# SCH_BlackRacer_team.net
KiCad netlist of a schematic drawn in EasyEDA
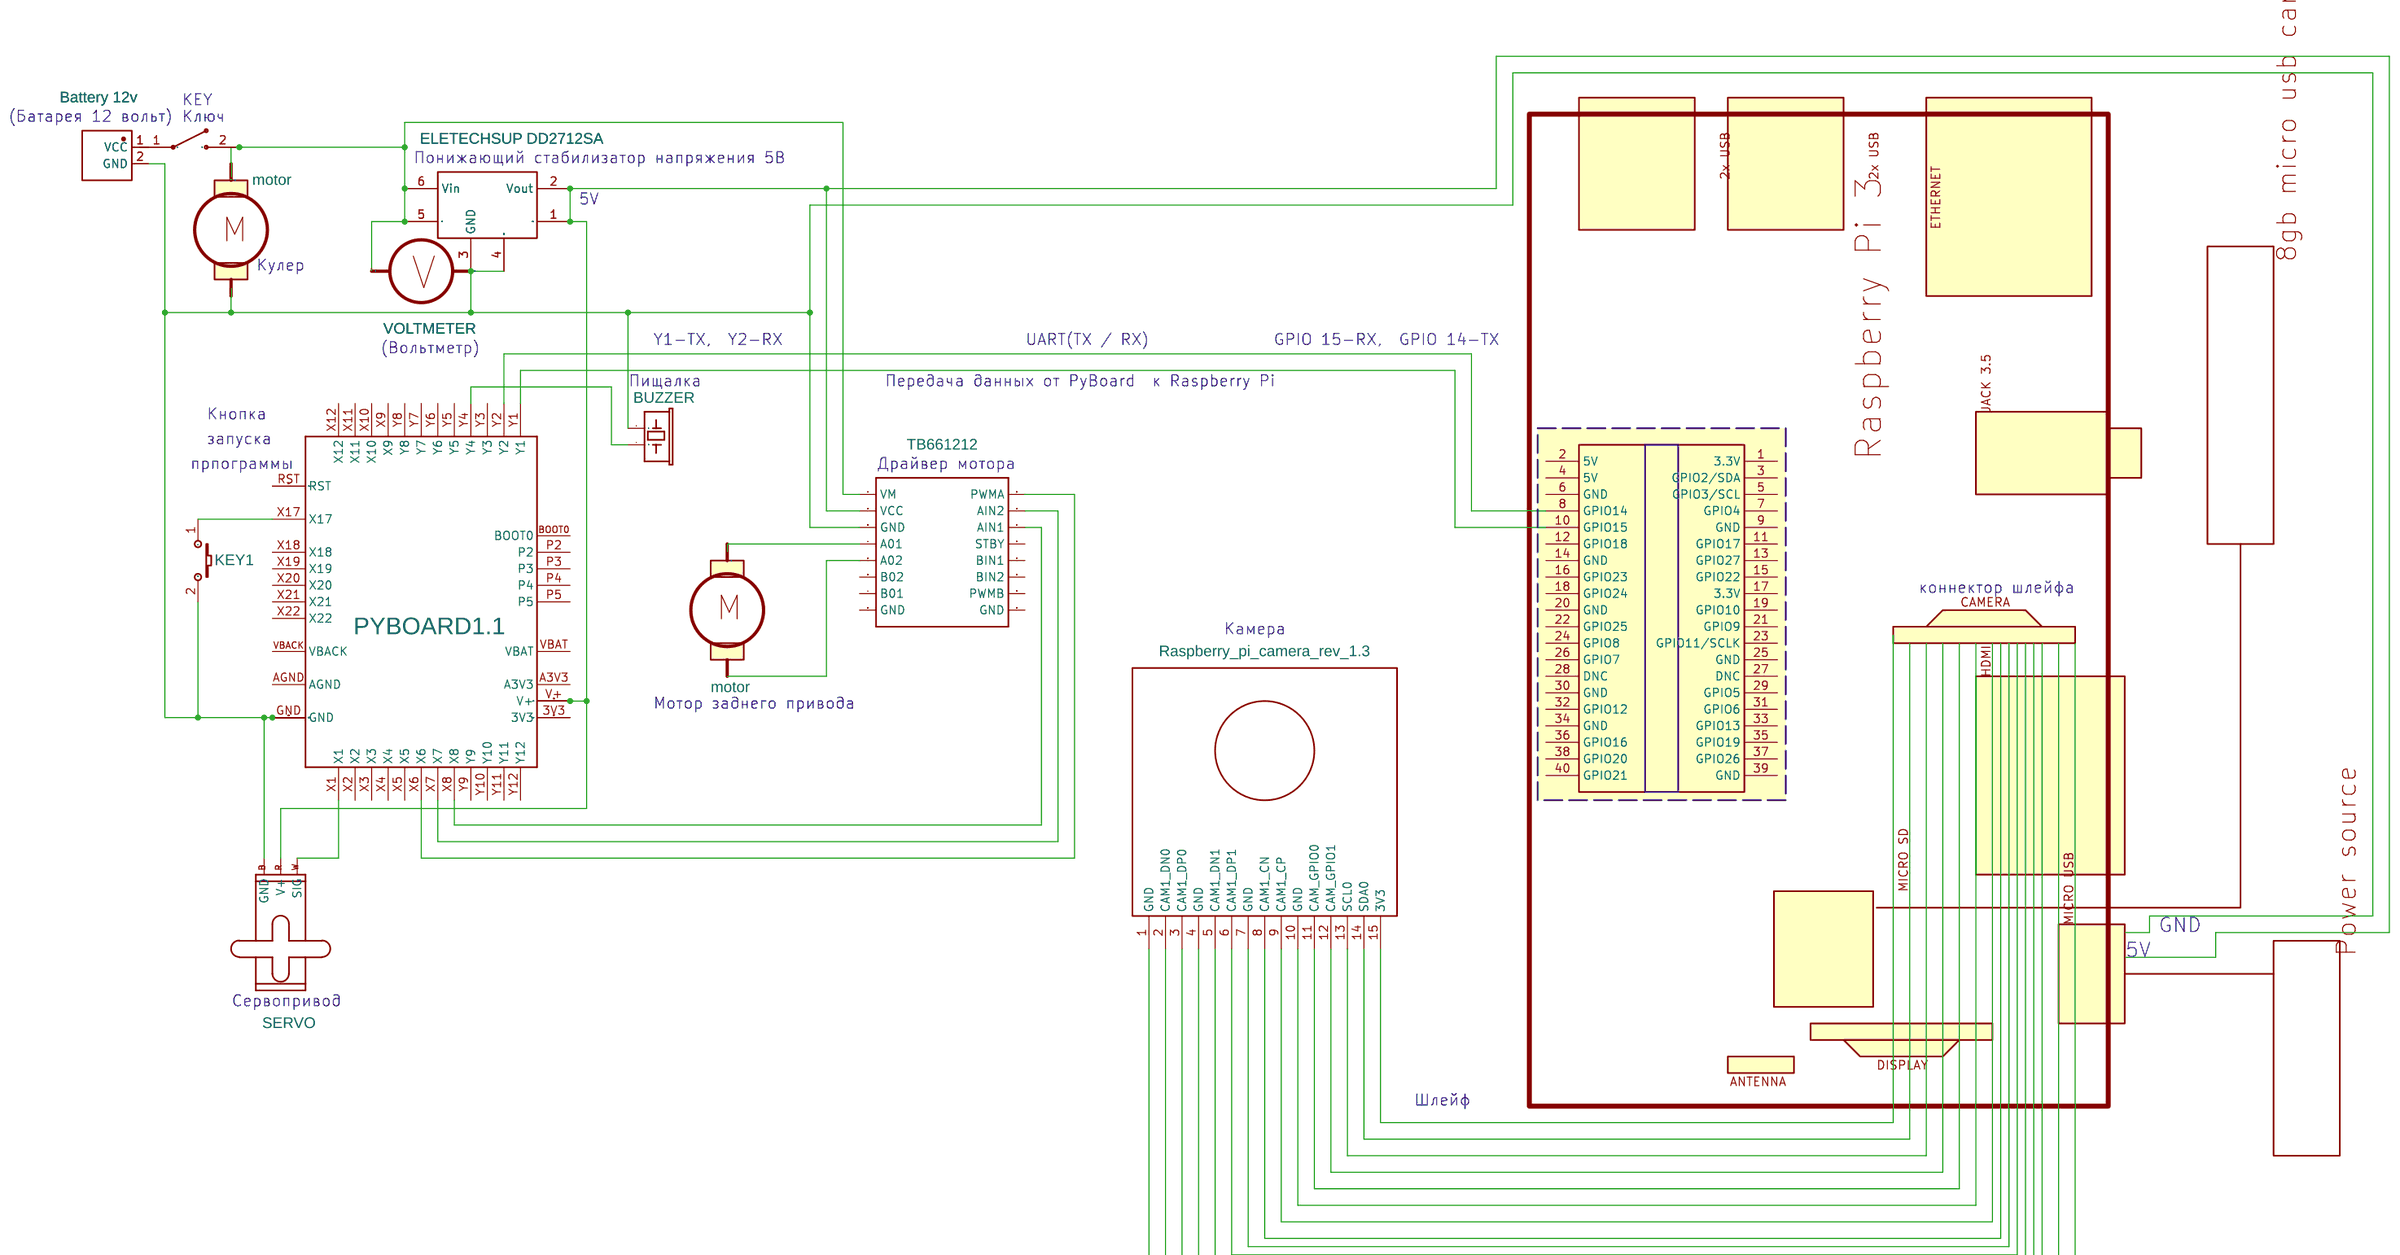
[diagram p0: schematic sheet]

(export (version "E")
  (design (tool "Eeschema 10.0.6"))
  (components
    (comp (ref "1") (value "PYBOARD1.1") (libsource (lib "") (part "PYBOARD1.1")))
    (comp (ref "KEY1")
      (value "K2-3.6×6.1_SMD")
      (fields
        (field (name "BOM_Manufacturer Part") "K2-1107ST-A4SW-06")
        (field (name "BOM_Supplier Part") "C118141")
      )
      (libsource (lib "") (part "K2-3.6×6.1_SMD"))
    )
    (comp (ref "M1") (value "SERVO") (libsource (lib "") (part "SERVO")))
    (comp (ref "M2") (value "motor") (libsource (lib "") (part "motor")))
    (comp (ref "M4") (value "motor") (libsource (lib "") (part "motor_1")))
    (comp (ref "P1") (value "VOLTMETER") (libsource (lib "") (part "VOLTMETER_XL")))
    (comp (ref "SG1") (value "BUZZER") (libsource (lib "") (part "BUZZER")))
    (comp (ref "U1") (value "ELETECHSUP DD2712SA") (libsource (lib "") (part "DD2712SA")))
    (comp (ref "U2")
      (value "Raspberry Pi")
      (fields
        (field (name "BOM_Manufacturer Part") "RASPBERRY PI 3 Model B")
        (field (name "BOM_Supplier Part") "Raspberry Pi 3-B")
      )
      (libsource (lib "") (part "Raspberry Pi"))
    )
    (comp (ref "U4") (value "Battery 12v") (libsource (lib "") (part "Battery")))
    (comp (ref "U5")
      (value "Raspberry_pi_camera_rev_1.3")
      (libsource (lib "") (part "Raspberry_pi_camera_rev_1.3"))
    )
    (comp (ref "U7")
      (value "Botton")
      (fields (field (name "BOM_Manufacturer Part") "2A080") (field (name "BOM_Supplier Part") "12131"))
      (libsource (lib "") (part "Botton"))
    )
    (comp (ref "U9") (value "TB661212") (libsource (lib "") (part "TB661212")))
  )
  (nets
    (net (code "1") (name "Net-(1-3V3-Pad3V3-1)") (class "Default")
      (node (ref "1") (pin "3V3") (pinfunction "3V3_3V3") (pintype "bidirectional"))
      (node (ref "1") (pin "3V3-1") (pinfunction "3V3_3V3-1") (pintype "bidirectional"))
    )
    (net (code "2") (name "Net-(1-PadRST)") (class "Default")
      (node (ref "1") (pin "RST") (pinfunction "RST_RST") (pintype "bidirectional"))
      (node (ref "1") (pin "RST1") (pinfunction "RST_RST1") (pintype "bidirectional"))
    )
    (net (code "3") (name "Net-(1-PadX17)") (class "Default")
      (node (ref "1") (pin "X17") (pinfunction "X17_X17") (pintype "bidirectional"))
      (node (ref "KEY1") (pin "1") (pinfunction "1_1") (pintype "unspecified"))
    )
    (net (code "4") (name "Net-(M1-GND)") (class "Default")
      (node (ref "1") (pin "GND") (pinfunction "GND_GND") (pintype "bidirectional"))
      (node (ref "1") (pin "GND0") (pinfunction "GND_GND0") (pintype "bidirectional"))
      (node (ref "1") (pin "GND1") (pinfunction "GND_GND1") (pintype "bidirectional"))
      (node (ref "1") (pin "GND2") (pinfunction "GND_GND2") (pintype "bidirectional"))
      (node (ref "1") (pin "GND3") (pinfunction "GND_GND3") (pintype "bidirectional"))
      (node (ref "1") (pin "GND4") (pinfunction "GND_GND4") (pintype "bidirectional"))
      (node (ref "1") (pin "GND5") (pinfunction "GND_GND5") (pintype "bidirectional"))
      (node (ref "1") (pin "GND6") (pinfunction "GND_GND6") (pintype "bidirectional"))
      (node (ref "KEY1") (pin "2") (pinfunction "2_2") (pintype "unspecified"))
      (node (ref "M1") (pin "3") (pinfunction "GND_3") (pintype "bidirectional"))
      (node (ref "P1") (pin "2") (pinfunction "B_2") (pintype "unspecified"))
      (node (ref "SG1") (pin "+") (pinfunction "1_+") (pintype "unspecified"))
      (node (ref "U1") (pin "3") (pinfunction "GND_3") (pintype "unspecified"))
      (node (ref "U1") (pin "4") (pinfunction "GND_4") (pintype "unspecified"))
      (node (ref "U4") (pin "2") (pinfunction "GND_2") (pintype "unspecified"))
      (node (ref "U9") (pin "GND") (pinfunction "GND_GND") (pintype "passive"))
    )
    (net (code "5") (name "Net-(M1-SIG)") (class "Default")
      (node (ref "1") (pin "X1") (pinfunction "X1_X1") (pintype "bidirectional"))
      (node (ref "M1") (pin "1") (pinfunction "SIG_1") (pintype "bidirectional"))
    )
    (net (code "6") (name "Net-(M1-V+)") (class "Default")
      (node (ref "1") (pin "V+") (pinfunction "V+_V+") (pintype "bidirectional"))
      (node (ref "1") (pin "V+1") (pinfunction "V+_V+1") (pintype "bidirectional"))
      (node (ref "1") (pin "V+2") (pinfunction "V+_V+2") (pintype "bidirectional"))
      (node (ref "1") (pin "V+3") (pinfunction "V+_V+3") (pintype "bidirectional"))
      (node (ref "1") (pin "V+4") (pinfunction "V+_V+4") (pintype "bidirectional"))
      (node (ref "1") (pin "V+5") (pinfunction "V+_V+5") (pintype "bidirectional"))
      (node (ref "1") (pin "V+6") (pinfunction "V+_V+6") (pintype "bidirectional"))
      (node (ref "M1") (pin "2") (pinfunction "V+_2") (pintype "bidirectional"))
      (node (ref "U1") (pin "1") (pinfunction "Vout_1") (pintype "unspecified"))
      (node (ref "U1") (pin "2") (pinfunction "Vout_2") (pintype "unspecified"))
      (node (ref "U9") (pin "VCC") (pinfunction "VCC_VCC") (pintype "passive"))
    )
    (net (code "7") (name "Net-(P1-A)") (class "Default")
      (node (ref "M2") (pin "2") (pinfunction "2_2") (pintype "unspecified"))
      (node (ref "P1") (pin "1") (pinfunction "A_1") (pintype "unspecified"))
      (node (ref "U1") (pin "5") (pinfunction "Vin_5") (pintype "unspecified"))
      (node (ref "U1") (pin "6") (pinfunction "Vin_6") (pintype "unspecified"))
      (node (ref "U7") (pin "2") (pinfunction "1_2") (pintype "unspecified"))
      (node (ref "U9") (pin "VM") (pinfunction "VM_VM") (pintype "passive"))
    )
    (net (code "8") (name "Net-(SG1-2)") (class "Default")
      (node (ref "1") (pin "Y4") (pinfunction "Y4_Y4") (pintype "bidirectional"))
      (node (ref "SG1") (pin "-") (pinfunction "2_-") (pintype "unspecified"))
    )
    (net (code "9") (name "Net-(U2-GPIO14)") (class "Default")
      (node (ref "1") (pin "Y2") (pinfunction "Y2_Y2") (pintype "bidirectional"))
      (node (ref "U2") (pin "8") (pinfunction "GPIO14_8") (pintype "bidirectional"))
    )
    (net (code "10") (name "Net-(U2-GPIO15)") (class "Default")
      (node (ref "1") (pin "Y1") (pinfunction "Y1_Y1") (pintype "bidirectional"))
      (node (ref "U2") (pin "10") (pinfunction "GPIO15_10") (pintype "bidirectional"))
    )
    (net (code "11") (name "Net-(U9-AIN1)") (class "Default")
      (node (ref "1") (pin "X8") (pinfunction "X8_X8") (pintype "bidirectional"))
      (node (ref "U9") (pin "14") (pinfunction "AIN1_14") (pintype "unspecified"))
    )
    (net (code "12") (name "Net-(U9-AIN2)") (class "Default")
      (node (ref "1") (pin "X7") (pinfunction "X7_X7") (pintype "bidirectional"))
      (node (ref "U9") (pin "15") (pinfunction "AIN2_15") (pintype "unspecified"))
    )
    (net (code "13") (name "Net-(U9-PWMA)") (class "Default")
      (node (ref "1") (pin "X6") (pinfunction "X6_X6") (pintype "bidirectional"))
      (node (ref "U9") (pin "16") (pinfunction "PWMA_16") (pintype "unspecified"))
    )
    (net (code "14") (name "unconnected-(1-PadA3V3)") (class "Default")
      (node (ref "1") (pin "A3V3") (pinfunction "A3V3_A3V3") (pintype "bidirectional"))
    )
    (net (code "15") (name "unconnected-(1-PadAGND)") (class "Default")
      (node (ref "1") (pin "AGND") (pinfunction "AGND_AGND") (pintype "bidirectional"))
    )
    (net (code "16") (name "unconnected-(1-PadBOOT0)") (class "Default")
      (node (ref "1") (pin "BOOT0") (pinfunction "BOOT0_BOOT0") (pintype "bidirectional"))
    )
    (net (code "17") (name "unconnected-(1-PadP2)") (class "Default")
      (node (ref "1") (pin "P2") (pinfunction "P2_P2") (pintype "bidirectional"))
    )
    (net (code "18") (name "unconnected-(1-PadP3)") (class "Default")
      (node (ref "1") (pin "P3") (pinfunction "P3_P3") (pintype "bidirectional"))
    )
    (net (code "19") (name "unconnected-(1-PadP4)") (class "Default")
      (node (ref "1") (pin "P4") (pinfunction "P4_P4") (pintype "bidirectional"))
    )
    (net (code "20") (name "unconnected-(1-PadP5)") (class "Default")
      (node (ref "1") (pin "P5") (pinfunction "P5_P5") (pintype "bidirectional"))
    )
    (net (code "21") (name "unconnected-(1-PadVBACK)") (class "Default")
      (node (ref "1") (pin "VBACK") (pinfunction "VBACK_VBACK") (pintype "bidirectional"))
    )
    (net (code "22") (name "unconnected-(1-PadVBAT)") (class "Default")
      (node (ref "1") (pin "VBAT") (pinfunction "VBAT_VBAT") (pintype "bidirectional"))
    )
    (net (code "23") (name "unconnected-(1-PadX2)") (class "Default")
      (node (ref "1") (pin "X2") (pinfunction "X2_X2") (pintype "bidirectional"))
    )
    (net (code "24") (name "unconnected-(1-PadX3)") (class "Default")
      (node (ref "1") (pin "X3") (pinfunction "X3_X3") (pintype "bidirectional"))
    )
    (net (code "25") (name "unconnected-(1-PadX4)") (class "Default")
      (node (ref "1") (pin "X4") (pinfunction "X4_X4") (pintype "bidirectional"))
    )
    (net (code "26") (name "unconnected-(1-PadX5)") (class "Default")
      (node (ref "1") (pin "X5") (pinfunction "X5_X5") (pintype "bidirectional"))
    )
    (net (code "27") (name "unconnected-(1-PadX9)") (class "Default")
      (node (ref "1") (pin "X9") (pinfunction "X9_X9") (pintype "bidirectional"))
    )
    (net (code "28") (name "unconnected-(1-PadX10)") (class "Default")
      (node (ref "1") (pin "X10") (pinfunction "X10_X10") (pintype "bidirectional"))
    )
    (net (code "29") (name "unconnected-(1-PadX11)") (class "Default")
      (node (ref "1") (pin "X11") (pinfunction "X11_X11") (pintype "bidirectional"))
    )
    (net (code "30") (name "unconnected-(1-PadX12)") (class "Default")
      (node (ref "1") (pin "X12") (pinfunction "X12_X12") (pintype "bidirectional"))
    )
    (net (code "31") (name "unconnected-(1-PadX18)") (class "Default")
      (node (ref "1") (pin "X18") (pinfunction "X18_X18") (pintype "bidirectional"))
    )
    (net (code "32") (name "unconnected-(1-PadX19)") (class "Default")
      (node (ref "1") (pin "X19") (pinfunction "X19_X19") (pintype "bidirectional"))
    )
    (net (code "33") (name "unconnected-(1-PadX20)") (class "Default")
      (node (ref "1") (pin "X20") (pinfunction "X20_X20") (pintype "bidirectional"))
    )
    (net (code "34") (name "unconnected-(1-PadX21)") (class "Default")
      (node (ref "1") (pin "X21") (pinfunction "X21_X21") (pintype "bidirectional"))
    )
    (net (code "35") (name "unconnected-(1-PadX22)") (class "Default")
      (node (ref "1") (pin "X22") (pinfunction "X22_X22") (pintype "bidirectional"))
    )
    (net (code "36") (name "unconnected-(1-PadY3)") (class "Default")
      (node (ref "1") (pin "Y3") (pinfunction "Y3_Y3") (pintype "bidirectional"))
    )
    (net (code "37") (name "unconnected-(1-PadY5)") (class "Default")
      (node (ref "1") (pin "Y5") (pinfunction "Y5_Y5") (pintype "bidirectional"))
    )
    (net (code "38") (name "unconnected-(1-PadY6)") (class "Default")
      (node (ref "1") (pin "Y6") (pinfunction "Y6_Y6") (pintype "bidirectional"))
    )
    (net (code "39") (name "unconnected-(1-PadY7)") (class "Default")
      (node (ref "1") (pin "Y7") (pinfunction "Y7_Y7") (pintype "bidirectional"))
    )
    (net (code "40") (name "unconnected-(1-PadY8)") (class "Default")
      (node (ref "1") (pin "Y8") (pinfunction "Y8_Y8") (pintype "bidirectional"))
    )
    (net (code "41") (name "unconnected-(1-PadY9)") (class "Default")
      (node (ref "1") (pin "Y9") (pinfunction "Y9_Y9") (pintype "bidirectional"))
    )
    (net (code "42") (name "unconnected-(1-PadY10)") (class "Default")
      (node (ref "1") (pin "Y10") (pinfunction "Y10_Y10") (pintype "bidirectional"))
    )
    (net (code "43") (name "unconnected-(1-PadY11)") (class "Default")
      (node (ref "1") (pin "Y11") (pinfunction "Y11_Y11") (pintype "bidirectional"))
    )
    (net (code "44") (name "unconnected-(1-PadY12)") (class "Default")
      (node (ref "1") (pin "Y12") (pinfunction "Y12_Y12") (pintype "bidirectional"))
    )
    (net (code "45") (name "unconnected-(M4-Pad2)") (class "Default")
      (node (ref "M4") (pin "2") (pinfunction "2_2") (pintype "unspecified"))
    )
    (net (code "46") (name "unconnected-(U2-3.3V-Pad1)") (class "Default")
      (node (ref "U2") (pin "1") (pinfunction "3.3V_1") (pintype "passive"))
    )
    (net (code "47") (name "unconnected-(U2-3.3V-Pad17)") (class "Default")
      (node (ref "U2") (pin "17") (pinfunction "3.3V_17") (pintype "passive"))
    )
    (net (code "48") (name "unconnected-(U2-5V-Pad2)") (class "Default")
      (node (ref "U2") (pin "2") (pinfunction "5V_2") (pintype "passive"))
    )
    (net (code "49") (name "unconnected-(U2-5V-Pad4)") (class "Default")
      (node (ref "U2") (pin "4") (pinfunction "5V_4") (pintype "passive"))
    )
    (net (code "50") (name "unconnected-(U2-DNC-Pad27)") (class "Default")
      (node (ref "U2") (pin "27") (pinfunction "DNC_27") (pintype "unspecified"))
    )
    (net (code "51") (name "unconnected-(U2-DNC-Pad28)") (class "Default")
      (node (ref "U2") (pin "28") (pinfunction "DNC_28") (pintype "unspecified"))
    )
    (net (code "52") (name "unconnected-(U2-GND-Pad6)") (class "Default")
      (node (ref "U2") (pin "6") (pinfunction "GND_6") (pintype "unspecified"))
    )
    (net (code "53") (name "unconnected-(U2-GND-Pad9)") (class "Default")
      (node (ref "U2") (pin "9") (pinfunction "GND_9") (pintype "unspecified"))
    )
    (net (code "54") (name "unconnected-(U2-GND-Pad14)") (class "Default")
      (node (ref "U2") (pin "14") (pinfunction "GND_14") (pintype "unspecified"))
    )
    (net (code "55") (name "unconnected-(U2-GND-Pad20)") (class "Default")
      (node (ref "U2") (pin "20") (pinfunction "GND_20") (pintype "unspecified"))
    )
    (net (code "56") (name "unconnected-(U2-GND-Pad25)") (class "Default")
      (node (ref "U2") (pin "25") (pinfunction "GND_25") (pintype "unspecified"))
    )
    (net (code "57") (name "unconnected-(U2-GND-Pad30)") (class "Default")
      (node (ref "U2") (pin "30") (pinfunction "GND_30") (pintype "unspecified"))
    )
    (net (code "58") (name "unconnected-(U2-GND-Pad34)") (class "Default")
      (node (ref "U2") (pin "34") (pinfunction "GND_34") (pintype "unspecified"))
    )
    (net (code "59") (name "unconnected-(U2-GND-Pad39)") (class "Default")
      (node (ref "U2") (pin "39") (pinfunction "GND_39") (pintype "unspecified"))
    )
    (net (code "60") (name "unconnected-(U2-GPIO2{slash}SDA-Pad3)") (class "Default")
      (node (ref "U2") (pin "3") (pinfunction "GPIO2/SDA_3") (pintype "bidirectional"))
    )
    (net (code "61") (name "unconnected-(U2-GPIO3{slash}SCL-Pad5)") (class "Default")
      (node (ref "U2") (pin "5") (pinfunction "GPIO3/SCL_5") (pintype "bidirectional"))
    )
    (net (code "62") (name "unconnected-(U2-GPIO4-Pad7)") (class "Default")
      (node (ref "U2") (pin "7") (pinfunction "GPIO4_7") (pintype "bidirectional"))
    )
    (net (code "63") (name "unconnected-(U2-GPIO5-Pad29)") (class "Default")
      (node (ref "U2") (pin "29") (pinfunction "GPIO5_29") (pintype "bidirectional"))
    )
    (net (code "64") (name "unconnected-(U2-GPIO6-Pad31)") (class "Default")
      (node (ref "U2") (pin "31") (pinfunction "GPIO6_31") (pintype "bidirectional"))
    )
    (net (code "65") (name "unconnected-(U2-GPIO7-Pad26)") (class "Default")
      (node (ref "U2") (pin "26") (pinfunction "GPIO7_26") (pintype "bidirectional"))
    )
    (net (code "66") (name "unconnected-(U2-GPIO8-Pad24)") (class "Default")
      (node (ref "U2") (pin "24") (pinfunction "GPIO8_24") (pintype "bidirectional"))
    )
    (net (code "67") (name "unconnected-(U2-GPIO9-Pad21)") (class "Default")
      (node (ref "U2") (pin "21") (pinfunction "GPIO9_21") (pintype "bidirectional"))
    )
    (net (code "68") (name "unconnected-(U2-GPIO10-Pad19)") (class "Default")
      (node (ref "U2") (pin "19") (pinfunction "GPIO10_19") (pintype "bidirectional"))
    )
    (net (code "69") (name "unconnected-(U2-GPIO11{slash}SCLK-Pad23)") (class "Default")
      (node (ref "U2") (pin "23") (pinfunction "GPIO11/SCLK_23") (pintype "bidirectional"))
    )
    (net (code "70") (name "unconnected-(U2-GPIO12-Pad32)") (class "Default")
      (node (ref "U2") (pin "32") (pinfunction "GPIO12_32") (pintype "bidirectional"))
    )
    (net (code "71") (name "unconnected-(U2-GPIO13-Pad33)") (class "Default")
      (node (ref "U2") (pin "33") (pinfunction "GPIO13_33") (pintype "bidirectional"))
    )
    (net (code "72") (name "unconnected-(U2-GPIO16-Pad36)") (class "Default")
      (node (ref "U2") (pin "36") (pinfunction "GPIO16_36") (pintype "bidirectional"))
    )
    (net (code "73") (name "unconnected-(U2-GPIO17-Pad11)") (class "Default")
      (node (ref "U2") (pin "11") (pinfunction "GPIO17_11") (pintype "bidirectional"))
    )
    (net (code "74") (name "unconnected-(U2-GPIO18-Pad12)") (class "Default")
      (node (ref "U2") (pin "12") (pinfunction "GPIO18_12") (pintype "bidirectional"))
    )
    (net (code "75") (name "unconnected-(U2-GPIO19-Pad35)") (class "Default")
      (node (ref "U2") (pin "35") (pinfunction "GPIO19_35") (pintype "bidirectional"))
    )
    (net (code "76") (name "unconnected-(U2-GPIO20-Pad38)") (class "Default")
      (node (ref "U2") (pin "38") (pinfunction "GPIO20_38") (pintype "bidirectional"))
    )
    (net (code "77") (name "unconnected-(U2-GPIO21-Pad40)") (class "Default")
      (node (ref "U2") (pin "40") (pinfunction "GPIO21_40") (pintype "bidirectional"))
    )
    (net (code "78") (name "unconnected-(U2-GPIO22-Pad15)") (class "Default")
      (node (ref "U2") (pin "15") (pinfunction "GPIO22_15") (pintype "bidirectional"))
    )
    (net (code "79") (name "unconnected-(U2-GPIO23-Pad16)") (class "Default")
      (node (ref "U2") (pin "16") (pinfunction "GPIO23_16") (pintype "bidirectional"))
    )
    (net (code "80") (name "unconnected-(U2-GPIO24-Pad18)") (class "Default")
      (node (ref "U2") (pin "18") (pinfunction "GPIO24_18") (pintype "bidirectional"))
    )
    (net (code "81") (name "unconnected-(U2-GPIO25-Pad22)") (class "Default")
      (node (ref "U2") (pin "22") (pinfunction "GPIO25_22") (pintype "bidirectional"))
    )
    (net (code "82") (name "unconnected-(U2-GPIO26-Pad37)") (class "Default")
      (node (ref "U2") (pin "37") (pinfunction "GPIO26_37") (pintype "bidirectional"))
    )
    (net (code "83") (name "unconnected-(U2-GPIO27-Pad13)") (class "Default")
      (node (ref "U2") (pin "13") (pinfunction "GPIO27_13") (pintype "bidirectional"))
    )
    (net (code "84") (name "unconnected-(U4-VCC-Pad1)") (class "Default")
      (node (ref "U4") (pin "1") (pinfunction "VCC_1") (pintype "unspecified"))
    )
    (net (code "85") (name "unconnected-(U5-3V3-Pad15)") (class "Default")
      (node (ref "U5") (pin "15") (pinfunction "3V3_15") (pintype "unspecified"))
    )
    (net (code "86") (name "unconnected-(U5-CAM1_CN-Pad8)") (class "Default")
      (node (ref "U5") (pin "8") (pinfunction "CAM1_CN_8") (pintype "unspecified"))
    )
    (net (code "87") (name "unconnected-(U5-CAM1_CP-Pad9)") (class "Default")
      (node (ref "U5") (pin "9") (pinfunction "CAM1_CP_9") (pintype "unspecified"))
    )
    (net (code "88") (name "unconnected-(U5-CAM1_DN0-Pad2)") (class "Default")
      (node (ref "U5") (pin "2") (pinfunction "CAM1_DN0_2") (pintype "unspecified"))
    )
    (net (code "89") (name "unconnected-(U5-CAM1_DN1-Pad5)") (class "Default")
      (node (ref "U5") (pin "5") (pinfunction "CAM1_DN1_5") (pintype "unspecified"))
    )
    (net (code "90") (name "unconnected-(U5-CAM1_DP0-Pad3)") (class "Default")
      (node (ref "U5") (pin "3") (pinfunction "CAM1_DP0_3") (pintype "unspecified"))
    )
    (net (code "91") (name "unconnected-(U5-CAM1_DP1-Pad6)") (class "Default")
      (node (ref "U5") (pin "6") (pinfunction "CAM1_DP1_6") (pintype "unspecified"))
    )
    (net (code "92") (name "unconnected-(U5-CAM_GPIO0-Pad11)") (class "Default")
      (node (ref "U5") (pin "11") (pinfunction "CAM_GPIO0_11") (pintype "unspecified"))
    )
    (net (code "93") (name "unconnected-(U5-CAM_GPIO1-Pad12)") (class "Default")
      (node (ref "U5") (pin "12") (pinfunction "CAM_GPIO1_12") (pintype "unspecified"))
    )
    (net (code "94") (name "unconnected-(U5-GND-Pad1)") (class "Default")
      (node (ref "U5") (pin "1") (pinfunction "GND_1") (pintype "unspecified"))
    )
    (net (code "95") (name "unconnected-(U5-GND-Pad4)") (class "Default")
      (node (ref "U5") (pin "4") (pinfunction "GND_4") (pintype "unspecified"))
    )
    (net (code "96") (name "unconnected-(U5-GND-Pad7)") (class "Default")
      (node (ref "U5") (pin "7") (pinfunction "GND_7") (pintype "unspecified"))
    )
    (net (code "97") (name "unconnected-(U5-GND-Pad10)") (class "Default")
      (node (ref "U5") (pin "10") (pinfunction "GND_10") (pintype "unspecified"))
    )
    (net (code "98") (name "unconnected-(U5-SCL0-Pad13)") (class "Default")
      (node (ref "U5") (pin "13") (pinfunction "SCL0_13") (pintype "unspecified"))
    )
    (net (code "99") (name "unconnected-(U5-SDA0-Pad14)") (class "Default")
      (node (ref "U5") (pin "14") (pinfunction "SDA0_14") (pintype "unspecified"))
    )
    (net (code "100") (name "unconnected-(U7-2-Pad1)") (class "Default")
      (node (ref "U7") (pin "1") (pinfunction "2_1") (pintype "unspecified"))
    )
    (net (code "101") (name "unconnected-(U9-A01-Pad4)") (class "Default")
      (node (ref "U9") (pin "4") (pinfunction "A01_4") (pintype "unspecified"))
    )
    (net (code "102") (name "unconnected-(U9-A02-Pad5)") (class "Default")
      (node (ref "U9") (pin "5") (pinfunction "A02_5") (pintype "unspecified"))
    )
    (net (code "103") (name "unconnected-(U9-B01-Pad7)") (class "Default")
      (node (ref "U9") (pin "7") (pinfunction "B01_7") (pintype "unspecified"))
    )
    (net (code "104") (name "unconnected-(U9-B02-Pad6)") (class "Default")
      (node (ref "U9") (pin "6") (pinfunction "B02_6") (pintype "unspecified"))
    )
    (net (code "105") (name "unconnected-(U9-BIN1-Pad12)") (class "Default")
      (node (ref "U9") (pin "12") (pinfunction "BIN1_12") (pintype "unspecified"))
    )
    (net (code "106") (name "unconnected-(U9-BIN2-Pad11)") (class "Default")
      (node (ref "U9") (pin "11") (pinfunction "BIN2_11") (pintype "unspecified"))
    )
    (net (code "107") (name "unconnected-(U9-GND-Pad8)") (class "Default")
      (node (ref "U9") (pin "8") (pinfunction "GND_8") (pintype "passive"))
    )
    (net (code "108") (name "unconnected-(U9-GND-Pad56)") (class "Default")
      (node (ref "U9") (pin "56") (pinfunction "GND_56") (pintype "passive"))
    )
    (net (code "109") (name "unconnected-(U9-PWMB-Pad10)") (class "Default")
      (node (ref "U9") (pin "10") (pinfunction "PWMB_10") (pintype "unspecified"))
    )
    (net (code "110") (name "unconnected-(U9-STBY-Pad13)") (class "Default")
      (node (ref "U9") (pin "13") (pinfunction "STBY_13") (pintype "unspecified"))
    )
  )
)
